# bme680_breakout_v01.net
KiCad netlist of a schematic drawn in EAGLE
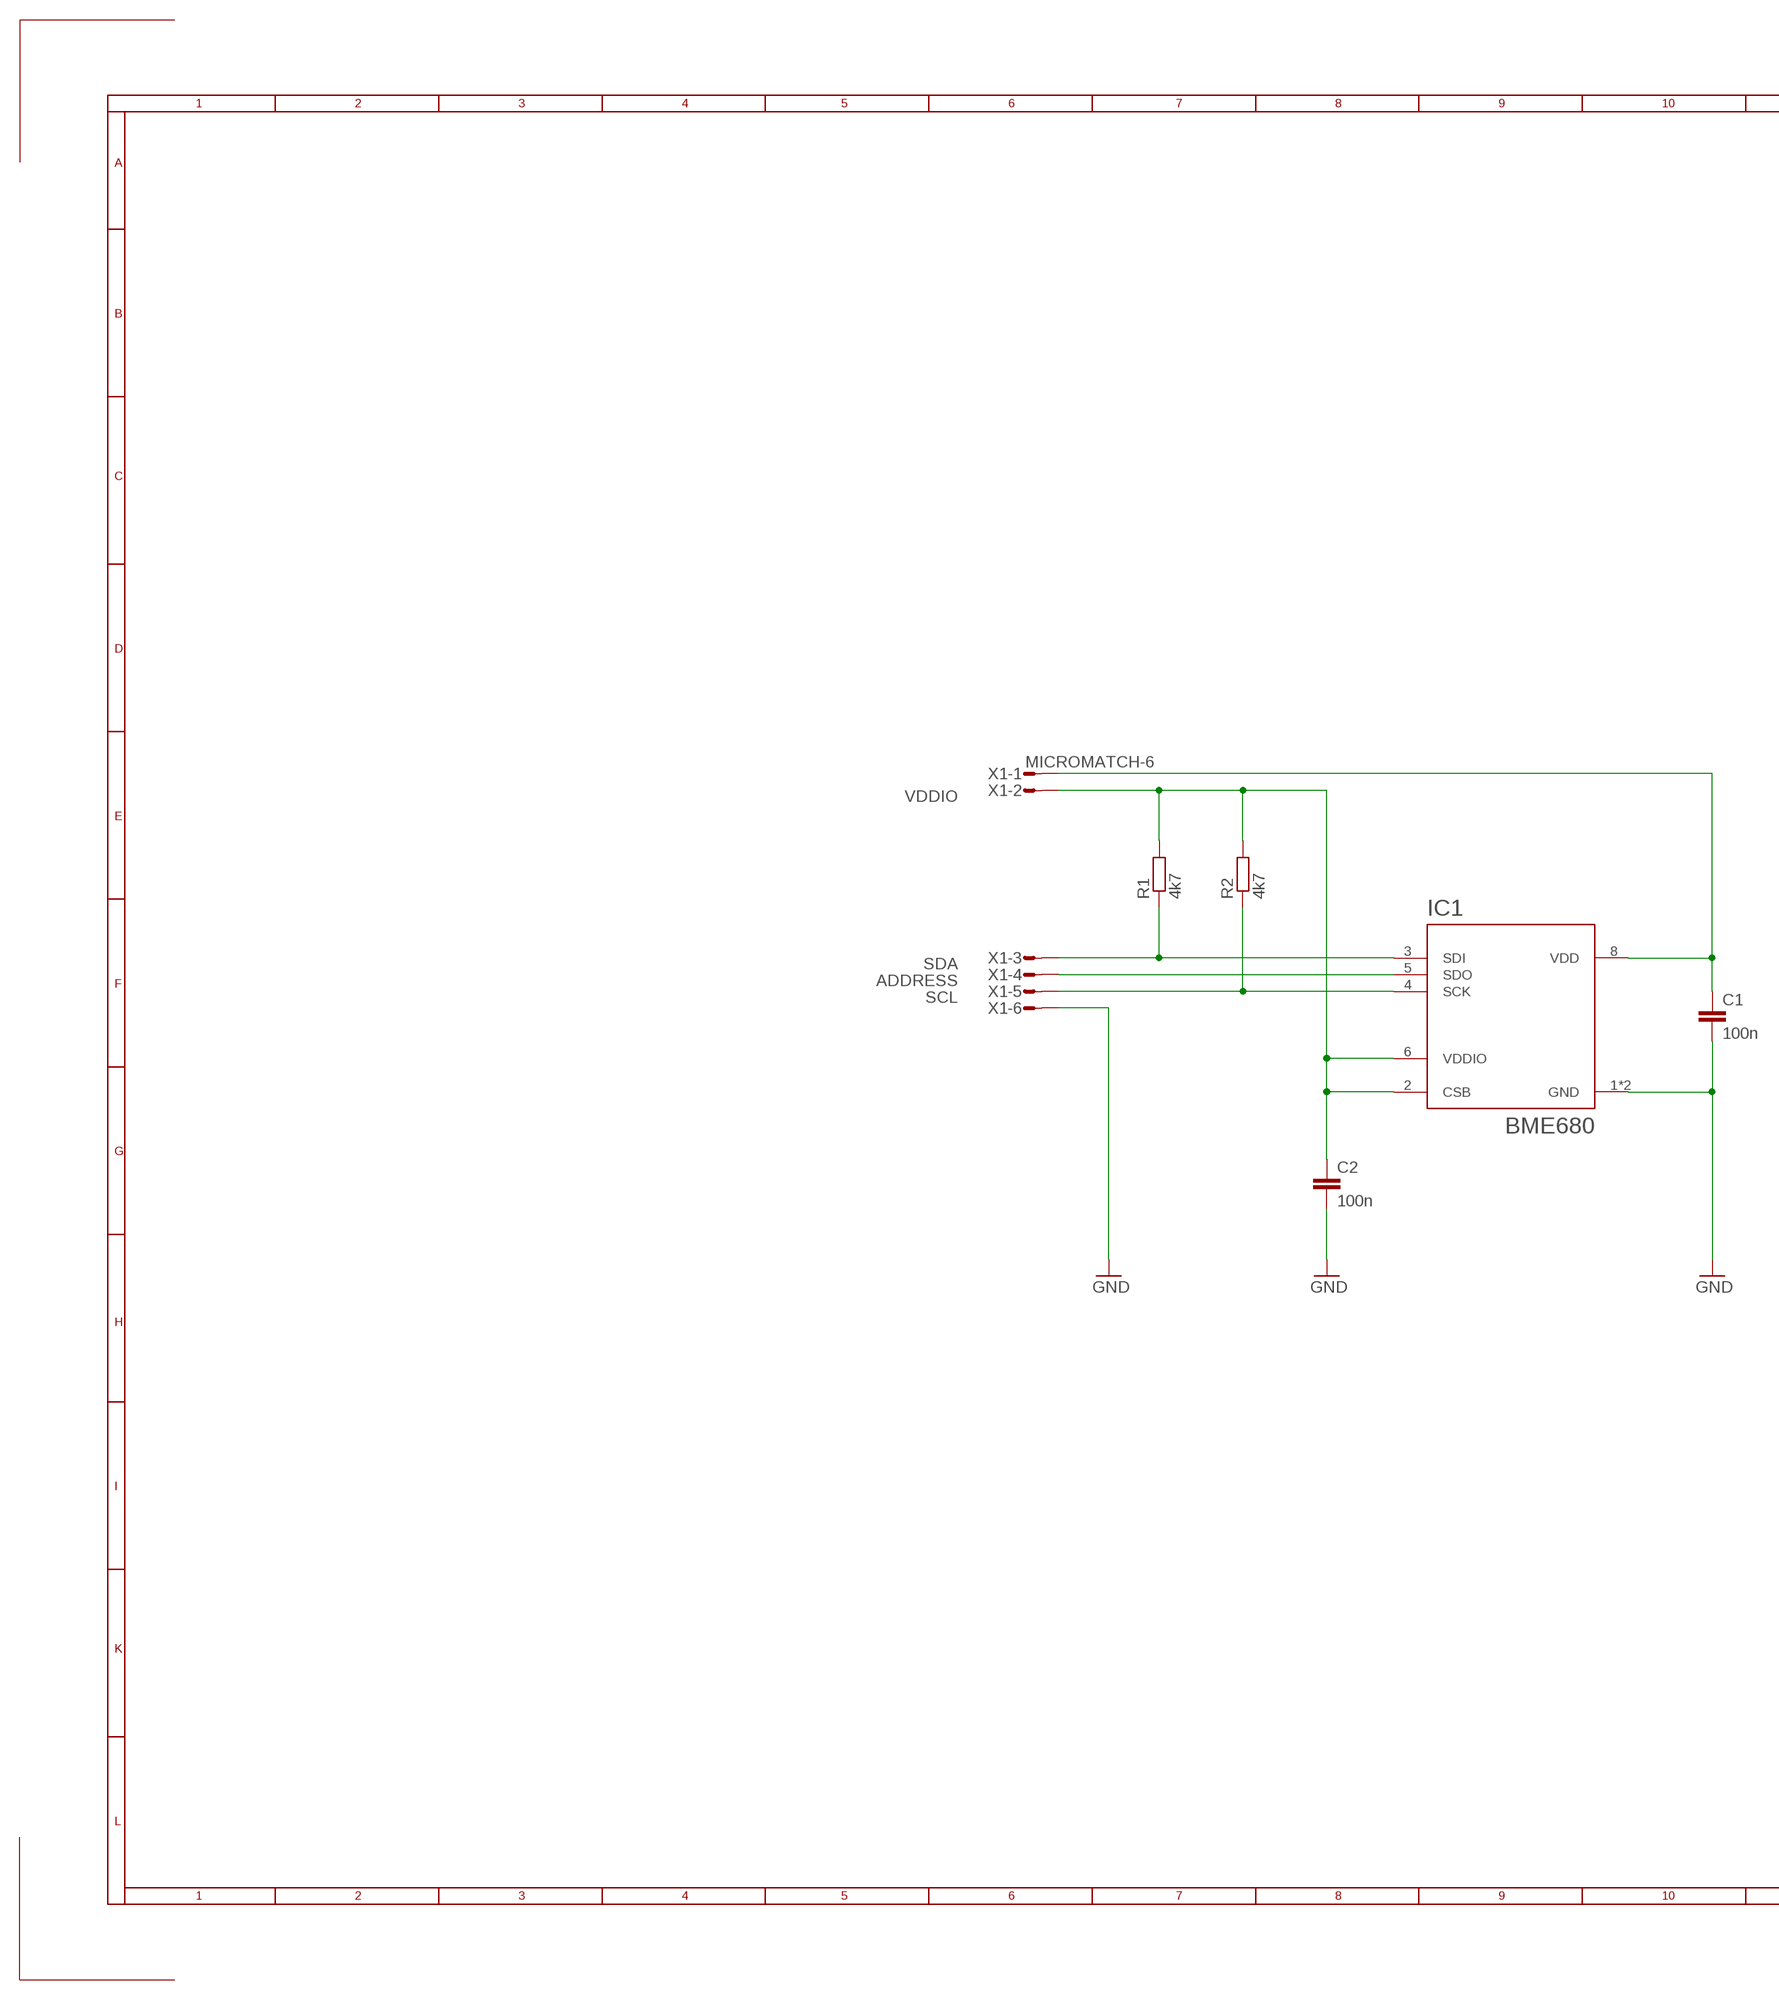
[diagram p0: schematic, sheet 1, part 1 of 2]
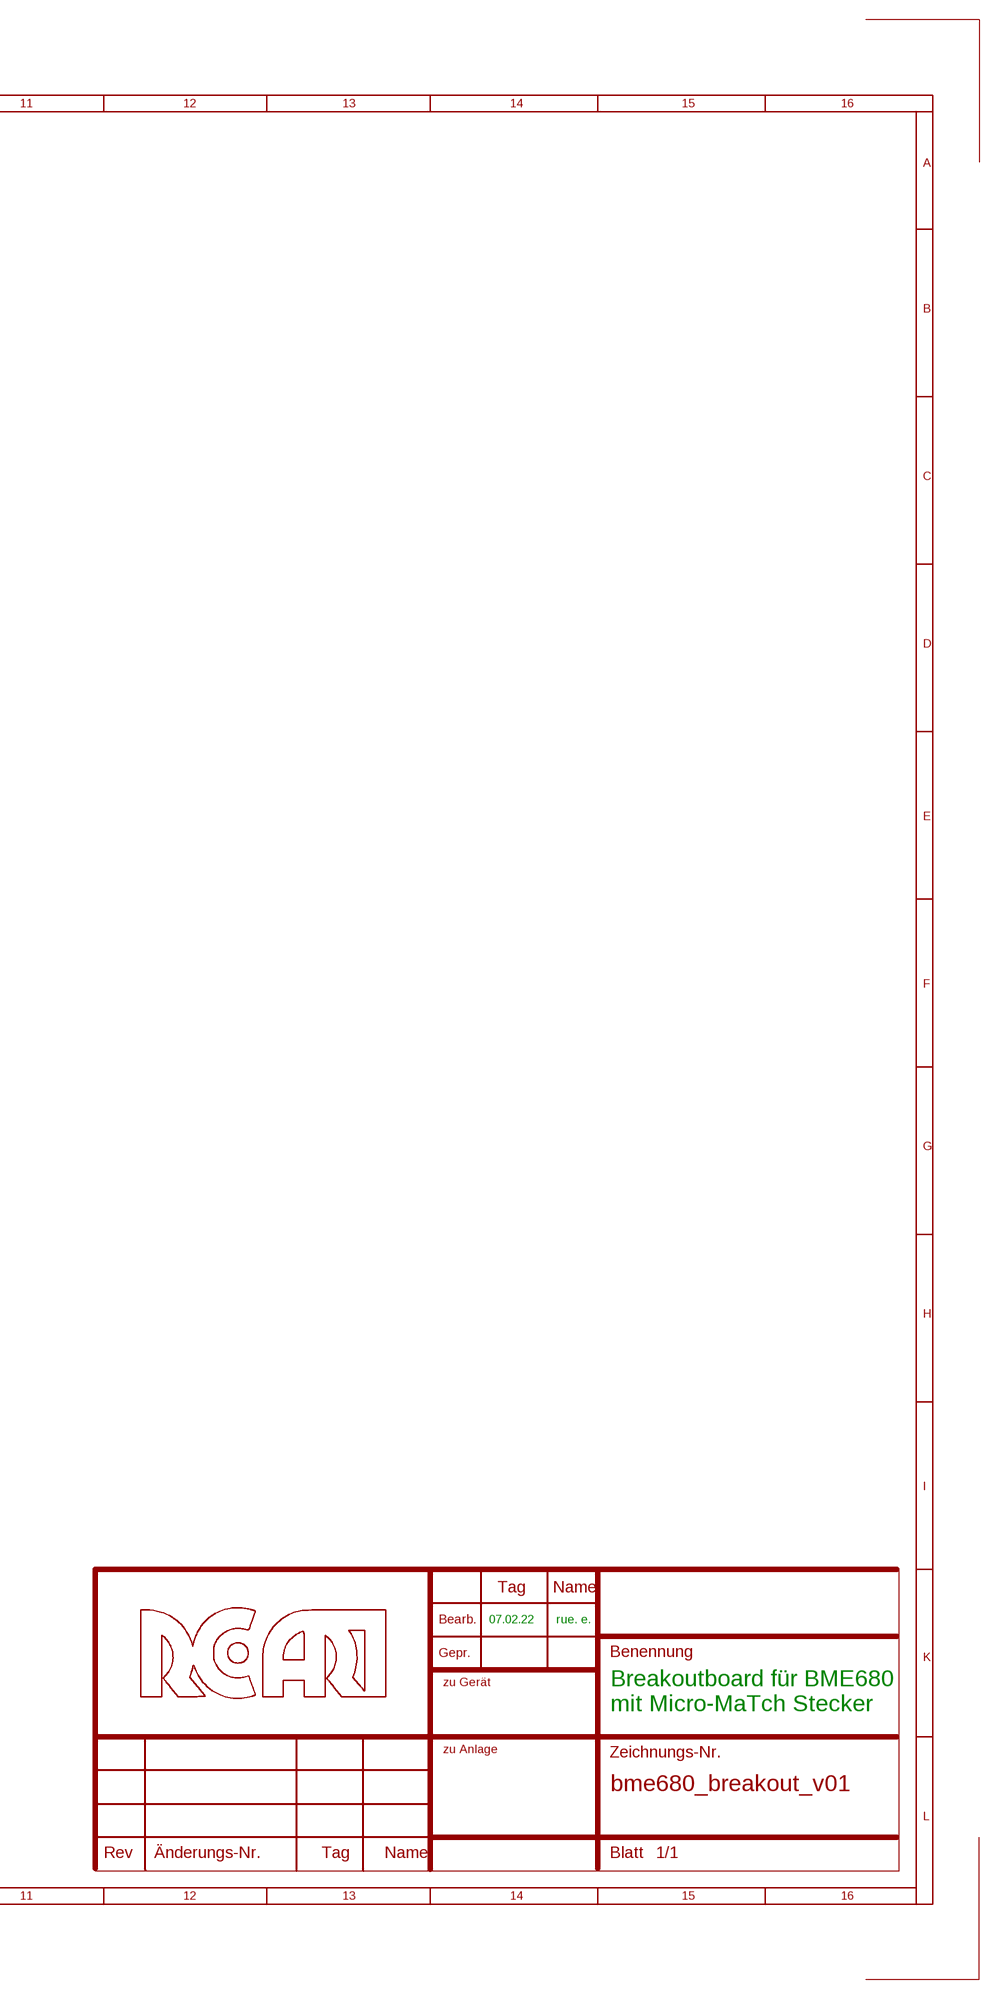
[diagram p1: schematic, sheet 1, part 2 of 2]

(export (version "E")
  (design (tool "Eeschema 10.0.6"))
  (components
    (comp (ref "C1")
      (value "100n")
      (footprint "eagle-import:C0805K")
      (libsource (lib "eagle-import") (part "C-EUC0805K"))
    )
    (comp (ref "C2")
      (value "100n")
      (footprint "eagle-import:C0805K")
      (libsource (lib "eagle-import") (part "C-EUC0805K"))
    )
    (comp (ref "IC1")
      (value "BME680")
      (footprint "eagle-import:LGA8")
      (libsource (lib "eagle-import") (part "BME680"))
    )
    (comp (ref "R1")
      (value "4k7")
      (footprint "eagle-import:R0603")
      (libsource (lib "eagle-import") (part "R-EU_R0603"))
    )
    (comp (ref "R2")
      (value "4k7")
      (footprint "eagle-import:R0603")
      (libsource (lib "eagle-import") (part "R-EU_R0603"))
    )
    (comp (ref "X1")
      (value "MICROMATCH-6")
      (footprint "eagle-import:MICROMATCH-6")
      (fields (field (name "MPN") "7-215464-6"))
      (libsource (lib "eagle-import") (part "MICROMATCH-6"))
    )
  )
  (nets
    (net (code "1") (name "/ADDRESS") (class "Default")
      (node (ref "IC1") (pin "5") (pinfunction "SDO_5") (pintype "bidirectional"))
      (node (ref "X1") (pin "4") (pinfunction "S_4") (pintype "passive"))
    )
    (net (code "2") (name "/SCL") (class "Default")
      (node (ref "IC1") (pin "4") (pinfunction "SCK_4") (pintype "bidirectional"))
      (node (ref "R2") (pin "1") (pinfunction "1_1") (pintype "passive"))
      (node (ref "X1") (pin "5") (pinfunction "S_5") (pintype "passive"))
    )
    (net (code "3") (name "/SDA") (class "Default")
      (node (ref "IC1") (pin "3") (pinfunction "SDI_3") (pintype "bidirectional"))
      (node (ref "R1") (pin "1") (pinfunction "1_1") (pintype "passive"))
      (node (ref "X1") (pin "3") (pinfunction "S_3") (pintype "passive"))
    )
    (net (code "4") (name "/VDDIO") (class "Default")
      (node (ref "C2") (pin "1") (pinfunction "1_1") (pintype "passive"))
      (node (ref "IC1") (pin "2") (pinfunction "CSB_2") (pintype "bidirectional"))
      (node (ref "IC1") (pin "6") (pinfunction "VDDIO_6") (pintype "bidirectional"))
      (node (ref "R1") (pin "2") (pinfunction "2_2") (pintype "passive"))
      (node (ref "R2") (pin "2") (pinfunction "2_2") (pintype "passive"))
      (node (ref "X1") (pin "2") (pinfunction "S_2") (pintype "passive"))
    )
    (net (code "5") (name "GND") (class "Default")
      (node (ref "C1") (pin "2") (pinfunction "2_2") (pintype "passive"))
      (node (ref "C2") (pin "2") (pinfunction "2_2") (pintype "passive"))
      (node (ref "IC1") (pin "1") (pinfunction "GND_1") (pintype "bidirectional"))
      (node (ref "IC1") (pin "7") (pinfunction "GND_7") (pintype "bidirectional"))
      (node (ref "X1") (pin "6") (pinfunction "S_6") (pintype "passive"))
    )
    (net (code "6") (name "Net-(IC1-VDD)") (class "Default")
      (node (ref "C1") (pin "1") (pinfunction "1_1") (pintype "passive"))
      (node (ref "IC1") (pin "8") (pinfunction "VDD_8") (pintype "bidirectional"))
      (node (ref "X1") (pin "1") (pinfunction "S_1") (pintype "passive"))
    )
  )
)
